# LED_Driver_Separate.net
KiCad netlist of a schematic drawn in EAGLE
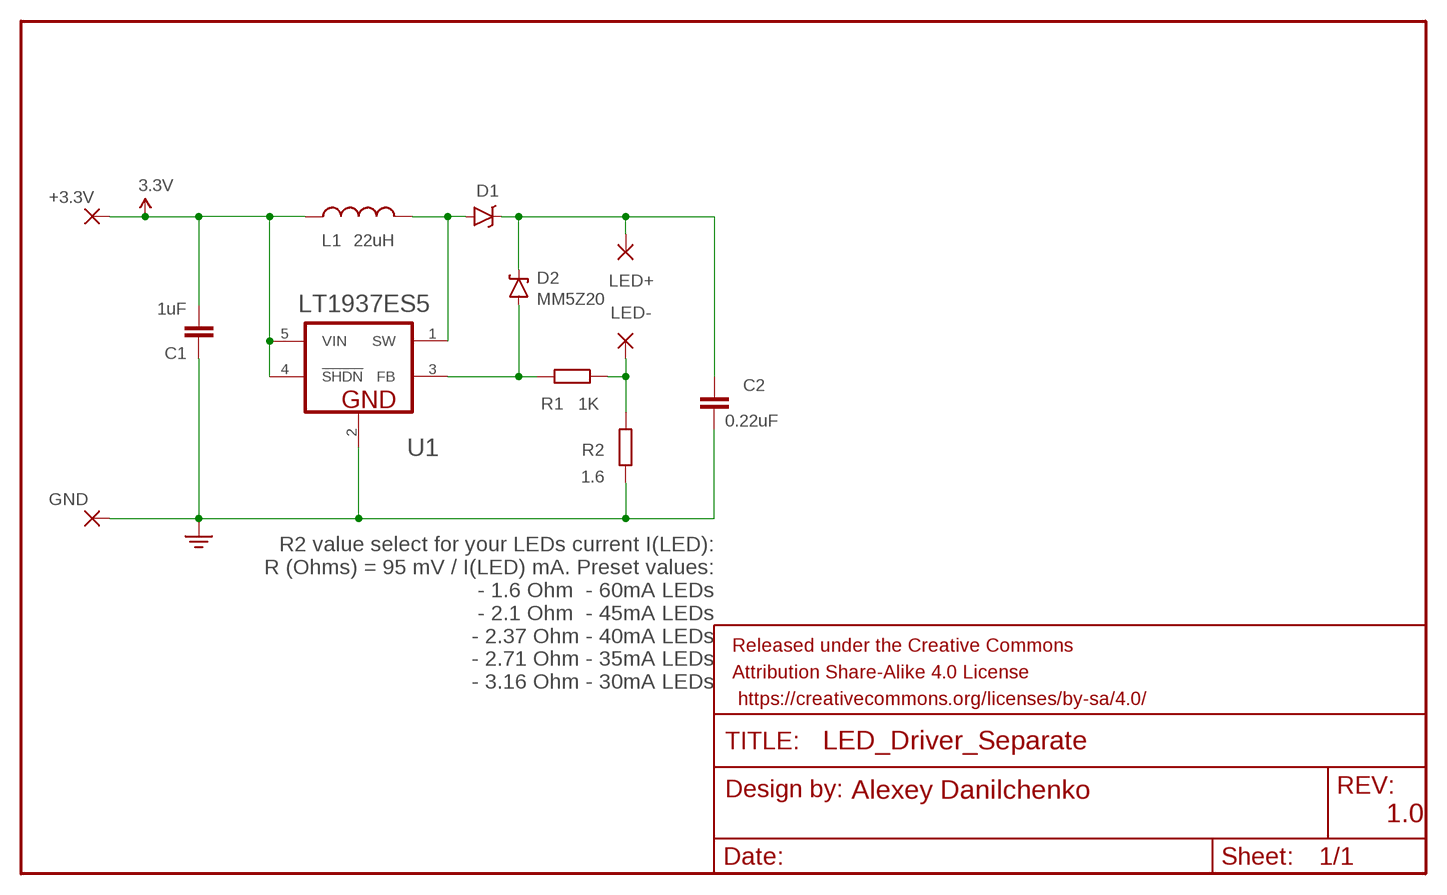
[diagram p0: schematic, sheet 1]

(export (version "E")
  (design (tool "Eeschema 10.0.6"))
  (components
    (comp (ref "+3.3V")
      (value "SMD2X2")
      (footprint "eagle-import:SMD2,54-2,54")
      (libsource (lib "eagle-import") (part "SMD2X2"))
    )
    (comp (ref "C1")
      (value "1uF")
      (footprint "eagle-import:C0805")
      (libsource (lib "eagle-import") (part "C-EUC0805"))
    )
    (comp (ref "C2")
      (value "0.22uF")
      (footprint "eagle-import:0603-CAP")
      (libsource (lib "eagle-import") (part "CAP0603-CAP"))
    )
    (comp (ref "D1")
      (value "RB751")
      (footprint "eagle-import:SOD-523")
      (libsource (lib "eagle-import") (part "DIODE-SCHOTTKY-RB751"))
    )
    (comp (ref "D2")
      (value "MM5Z20")
      (footprint "eagle-import:SOD-523")
      (libsource (lib "eagle-import") (part "DIODE-ZENERSOD-523Z"))
    )
    (comp (ref "FRAME1")
      (value "FRAME-LEDGER")
      (footprint "eagle-import:CREATIVE_COMMONS")
      (fields (field (name "AUTHOR") "Alexey Danilchenko") (field (name "VER") "1.0"))
      (libsource (lib "eagle-import") (part "FRAME-LEDGER"))
    )
    (comp (ref "GND")
      (value "SMD2X2")
      (footprint "eagle-import:SMD2,54-2,54")
      (libsource (lib "eagle-import") (part "SMD2X2"))
    )
    (comp (ref "L1")
      (value "22uH")
      (footprint "eagle-import:1210")
      (libsource (lib "eagle-import") (part "INDUCTOR1210"))
    )
    (comp (ref "LED+")
      (value "SMD2X2")
      (footprint "eagle-import:SMD2,54-2,54")
      (libsource (lib "eagle-import") (part "SMD2X2"))
    )
    (comp (ref "LED-")
      (value "SMD2X2")
      (footprint "eagle-import:SMD2,54-2,54")
      (libsource (lib "eagle-import") (part "SMD2X2"))
    )
    (comp (ref "R1")
      (value "1K")
      (footprint "eagle-import:R0805")
      (libsource (lib "eagle-import") (part "R-EU_R0805"))
    )
    (comp (ref "R2")
      (value "1.6")
      (footprint "eagle-import:M1206")
      (libsource (lib "eagle-import") (part "rcl_334_R-EU_M1206"))
    )
    (comp (ref "U1")
      (value "LT1937ES5")
      (footprint "eagle-import:LINEAR_TECHNOLOGY_LT1937ES5#TRMPBF_1")
      (fields (field (name "MF") "Linear Technology") (field (name "MPN") "LT1937ES5#TRMPBF"))
      (libsource (lib "eagle-import") (part "LINEAR_TECHNOLOGY_LT1937ES5#TRMPBFLINEAR_TECHNOLOGY_LT1937ES5#TRMPBF_0_1"))
    )
  )
  (nets
    (net (code "1") (name "3.3V") (class "Default")
      (node (ref "+3.3V") (pin "1") (pinfunction "P_1") (pintype "passive"))
      (node (ref "C1") (pin "1") (pinfunction "1_1") (pintype "passive"))
      (node (ref "L1") (pin "1") (pinfunction "1_1") (pintype "passive"))
      (node (ref "U1") (pin "4") (pinfunction "~{SHDN}_4") (pintype "input"))
      (node (ref "U1") (pin "5") (pinfunction "VIN_5") (pintype "power_in"))
    )
    (net (code "2") (name "GND") (class "Default")
      (node (ref "C1") (pin "2") (pinfunction "2_2") (pintype "passive"))
      (node (ref "C2") (pin "2") (pinfunction "2_2") (pintype "passive"))
      (node (ref "GND") (pin "1") (pinfunction "P_1") (pintype "passive"))
      (node (ref "R2") (pin "1") (pinfunction "1_1") (pintype "passive"))
      (node (ref "U1") (pin "2") (pinfunction "GND_2") (pintype "power_in"))
    )
    (net (code "3") (name "Net-(LED+-P)") (class "Default")
      (node (ref "C2") (pin "1") (pinfunction "1_1") (pintype "passive"))
      (node (ref "D1") (pin "C") (pinfunction "C_C") (pintype "passive"))
      (node (ref "D2") (pin "C") (pinfunction "C_C") (pintype "passive"))
      (node (ref "LED+") (pin "1") (pinfunction "P_1") (pintype "passive"))
    )
    (net (code "4") (name "Net-(LED--P)") (class "Default")
      (node (ref "LED-") (pin "1") (pinfunction "P_1") (pintype "passive"))
      (node (ref "R1") (pin "1") (pinfunction "1_1") (pintype "passive"))
      (node (ref "R2") (pin "2") (pinfunction "2_2") (pintype "passive"))
    )
    (net (code "5") (name "Net-(U1-FB)") (class "Default")
      (node (ref "D2") (pin "A") (pinfunction "A_A") (pintype "passive"))
      (node (ref "R1") (pin "2") (pinfunction "2_2") (pintype "passive"))
      (node (ref "U1") (pin "3") (pinfunction "FB_3") (pintype "input"))
    )
    (net (code "6") (name "Net-(U1-SW)") (class "Default")
      (node (ref "D1") (pin "A") (pinfunction "A_A") (pintype "passive"))
      (node (ref "L1") (pin "2") (pinfunction "2_2") (pintype "passive"))
      (node (ref "U1") (pin "1") (pinfunction "SW_1") (pintype "power_in"))
    )
  )
)
